# focuser-1_6.net
KiCad netlist of a schematic drawn in EAGLE
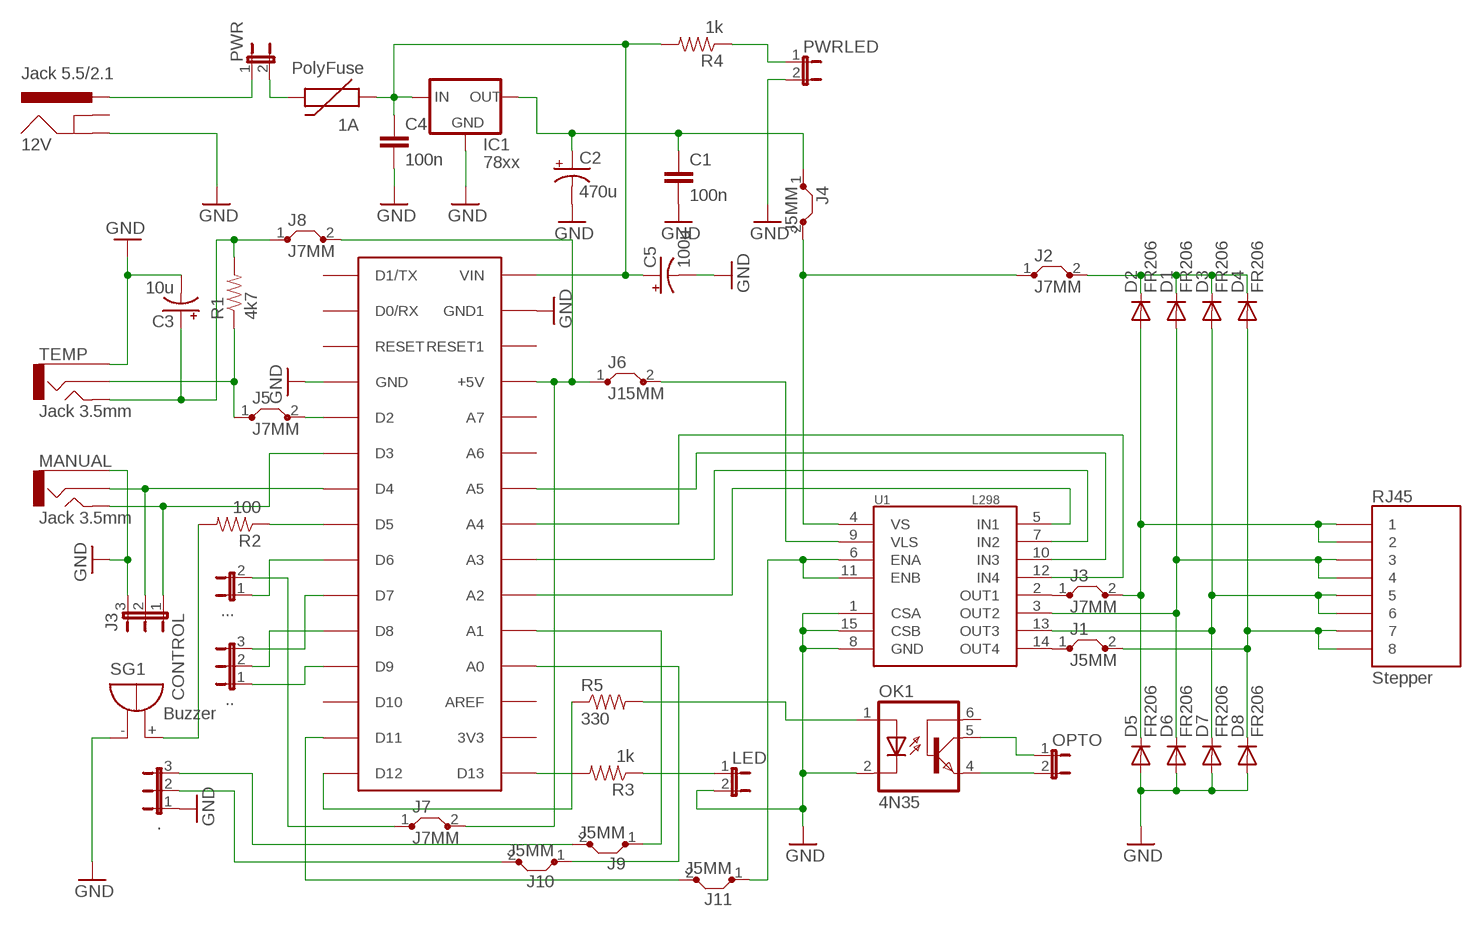
[diagram p0: schematic, sheet 1]

(export (version "E")
  (design (tool "Eeschema 10.0.6"))
  (components
    (comp (ref ".")
      (value "JUMPER-3PTH")
      (footprint "eagle-import:1X03")
      (libsource (lib "eagle-import") (part "JUMPER-3PTH"))
    )
    (comp (ref "..")
      (value "JUMPER-3PTH")
      (footprint "eagle-import:1X03")
      (libsource (lib "eagle-import") (part "JUMPER-3PTH"))
    )
    (comp (ref "...")
      (value "JUMPER-2PTH")
      (footprint "eagle-import:1X02")
      (libsource (lib "eagle-import") (part "JUMPER-2PTH"))
    )
    (comp (ref "1A")
      (value "PolyFuse")
      (footprint "eagle-import:PTC")
      (libsource (lib "eagle-import") (part "PTCPTH"))
    )
    (comp (ref "12V")
      (value "Jack 5.5/2.1")
      (footprint "eagle-import:POWER_JACK_COMBO")
      (libsource (lib "eagle-import") (part "POWER_JACKCOMBO"))
    )
    (comp (ref "C1")
      (value "100n")
      (footprint "eagle-import:AXIAL-5MM")
      (libsource (lib "eagle-import") (part "CAP_"))
    )
    (comp (ref "C2")
      (value "470u")
      (footprint "eagle-import:CPOL-RADIAL-100UF-25V")
      (libsource (lib "eagle-import") (part "CAP_POLPTH1"))
    )
    (comp (ref "C3")
      (value "10u")
      (footprint "eagle-import:CPOL-RADIAL-100UF-25V")
      (libsource (lib "eagle-import") (part "CAP_POLPTH1"))
    )
    (comp (ref "C4")
      (value "100n")
      (footprint "eagle-import:AXIAL-5MM")
      (libsource (lib "eagle-import") (part "CAP_"))
    )
    (comp (ref "C5")
      (value "100u")
      (footprint "eagle-import:CPOL-RADIAL-100UF-25V")
      (libsource (lib "eagle-import") (part "CAP_POLPTH1"))
    )
    (comp (ref "CONTROL")
      (value "J3")
      (footprint "eagle-import:1X03")
      (libsource (lib "eagle-import") (part "JUMPER-3PTH"))
    )
    (comp (ref "D1")
      (value "FR206")
      (footprint "eagle-import:DIODE-1N4001")
      (libsource (lib "eagle-import") (part "DIODEPTH"))
    )
    (comp (ref "D2")
      (value "FR206")
      (footprint "eagle-import:DIODE-1N4001")
      (libsource (lib "eagle-import") (part "DIODEPTH"))
    )
    (comp (ref "D3")
      (value "FR206")
      (footprint "eagle-import:DIODE-1N4001")
      (libsource (lib "eagle-import") (part "DIODEPTH"))
    )
    (comp (ref "D4")
      (value "FR206")
      (footprint "eagle-import:DIODE-1N4001")
      (libsource (lib "eagle-import") (part "DIODEPTH"))
    )
    (comp (ref "D5")
      (value "FR206")
      (footprint "eagle-import:DIODE-1N4001")
      (libsource (lib "eagle-import") (part "DIODEPTH"))
    )
    (comp (ref "D6")
      (value "FR206")
      (footprint "eagle-import:DIODE-1N4001")
      (libsource (lib "eagle-import") (part "DIODEPTH"))
    )
    (comp (ref "D7")
      (value "FR206")
      (footprint "eagle-import:DIODE-1N4001")
      (libsource (lib "eagle-import") (part "DIODEPTH"))
    )
    (comp (ref "D8")
      (value "FR206")
      (footprint "eagle-import:DIODE-1N4001")
      (libsource (lib "eagle-import") (part "DIODEPTH"))
    )
    (comp (ref "IC1")
      (value "78xx")
      (footprint "eagle-import:TO220-IGO")
      (libsource (lib "eagle-import") (part "V_REG_78XXSINK"))
    )
    (comp (ref "J1")
      (value "J5MM")
      (footprint "eagle-import:05")
      (libsource (lib "eagle-import") (part "J5MM"))
    )
    (comp (ref "J2")
      (value "J7MM")
      (footprint "eagle-import:07")
      (libsource (lib "eagle-import") (part "J7MM"))
    )
    (comp (ref "J3")
      (value "J7MM")
      (footprint "eagle-import:07")
      (libsource (lib "eagle-import") (part "J7MM"))
    )
    (comp (ref "J4")
      (value "J5MM")
      (footprint "eagle-import:05")
      (libsource (lib "eagle-import") (part "J5MM"))
    )
    (comp (ref "J5")
      (value "J7MM")
      (footprint "eagle-import:07")
      (libsource (lib "eagle-import") (part "J7MM"))
    )
    (comp (ref "J6")
      (value "J15MM")
      (footprint "eagle-import:15")
      (libsource (lib "eagle-import") (part "J15MM"))
    )
    (comp (ref "J7")
      (value "J7MM")
      (footprint "eagle-import:07")
      (libsource (lib "eagle-import") (part "J7MM"))
    )
    (comp (ref "J8")
      (value "J7MM")
      (footprint "eagle-import:07")
      (libsource (lib "eagle-import") (part "J7MM"))
    )
    (comp (ref "J9")
      (value "J5MM")
      (footprint "eagle-import:05")
      (libsource (lib "eagle-import") (part "J5MM"))
    )
    (comp (ref "J10")
      (value "J5MM")
      (footprint "eagle-import:05")
      (libsource (lib "eagle-import") (part "J5MM"))
    )
    (comp (ref "J11")
      (value "J5MM")
      (footprint "eagle-import:05")
      (libsource (lib "eagle-import") (part "J5MM"))
    )
    (comp (ref "LED")
      (value "JUMPER-2PTH")
      (footprint "eagle-import:1X02")
      (libsource (lib "eagle-import") (part "JUMPER-2PTH"))
    )
    (comp (ref "MANUAL")
      (value "Jack 3.5mm")
      (footprint "eagle-import:AUDIO-JACK")
      (libsource (lib "eagle-import") (part "AUDIO-JACKPTH"))
    )
    (comp (ref "OK1")
      (value "4N35")
      (footprint "eagle-import:DIL06")
      (fields (field (name "MF") "FAIRCHILD SEMICONDUCTOR"))
      (libsource (lib "eagle-import") (part "4N35"))
    )
    (comp (ref "OPTO")
      (value "JUMPER-2PTH")
      (footprint "eagle-import:1X02")
      (libsource (lib "eagle-import") (part "JUMPER-2PTH"))
    )
    (comp (ref "PWR")
      (value "JUMPER-2PTH")
      (footprint "eagle-import:1X02")
      (libsource (lib "eagle-import") (part "JUMPER-2PTH"))
    )
    (comp (ref "PWRLED")
      (value "JUMPER-2PTH")
      (footprint "eagle-import:1X02")
      (libsource (lib "eagle-import") (part "JUMPER-2PTH"))
    )
    (comp (ref "R1")
      (value "4k7")
      (footprint "eagle-import:AXIAL-0.3")
      (libsource (lib "eagle-import") (part "RESISTORPTH1"))
    )
    (comp (ref "R2")
      (value "100")
      (footprint "eagle-import:AXIAL-0.3")
      (libsource (lib "eagle-import") (part "RESISTORPTH1"))
    )
    (comp (ref "R3")
      (value "1k")
      (footprint "eagle-import:AXIAL-0.3")
      (libsource (lib "eagle-import") (part "RESISTORPTH1"))
    )
    (comp (ref "R4")
      (value "1k")
      (footprint "eagle-import:AXIAL-0.3")
      (libsource (lib "eagle-import") (part "RESISTORPTH1"))
    )
    (comp (ref "R5")
      (value "330")
      (footprint "eagle-import:AXIAL-0.3")
      (libsource (lib "eagle-import") (part "RESISTORPTH1"))
    )
    (comp (ref "RJ45")
      (value "Stepper")
      (footprint "eagle-import:RJ45-8")
      (libsource (lib "eagle-import") (part "RJ45-8PTH"))
    )
    (comp (ref "SG1")
      (value "Buzzer")
      (footprint "eagle-import:F_QMBIII")
      (libsource (lib "eagle-import") (part "F/QMBIII"))
    )
    (comp (ref "TEMP")
      (value "Jack 3.5mm")
      (footprint "eagle-import:AUDIO-JACK")
      (libsource (lib "eagle-import") (part "AUDIO-JACKPTH"))
    )
    (comp (ref "U$1")
      (value "ARDUINONANO")
      (footprint "eagle-import:PDIP-32")
      (libsource (lib "eagle-import") (part "ARDUINONANO"))
    )
    (comp (ref "U1")
      (value "L298")
      (footprint "eagle-import:MULTIWATT15")
      (libsource (lib "eagle-import") (part "L298"))
    )
  )
  (nets
    (net (code "1") (name "GND") (class "Default")
      (node (ref ".") (pin "1") (pinfunction "1_1") (pintype "passive"))
      (node (ref "12V") (pin "GND@1") (pinfunction "GND_GND@1") (pintype "bidirectional"))
      (node (ref "C1") (pin "P$2") (pinfunction "2_P$2") (pintype "passive"))
      (node (ref "C2") (pin "2") (pinfunction "-_2") (pintype "passive"))
      (node (ref "C3") (pin "2") (pinfunction "-_2") (pintype "passive"))
      (node (ref "C4") (pin "P$2") (pinfunction "2_P$2") (pintype "passive"))
      (node (ref "C5") (pin "2") (pinfunction "-_2") (pintype "passive"))
      (node (ref "CONTROL") (pin "3") (pinfunction "3_3") (pintype "passive"))
      (node (ref "D5") (pin "A") (pinfunction "A_A") (pintype "passive"))
      (node (ref "D6") (pin "A") (pinfunction "A_A") (pintype "passive"))
      (node (ref "D7") (pin "A") (pinfunction "A_A") (pintype "passive"))
      (node (ref "D8") (pin "A") (pinfunction "A_A") (pintype "passive"))
      (node (ref "IC1") (pin "GND") (pinfunction "GND_GND") (pintype "input"))
      (node (ref "LED") (pin "2") (pinfunction "2_2") (pintype "passive"))
      (node (ref "MANUAL") (pin "1") (pinfunction "1_1") (pintype "bidirectional"))
      (node (ref "OK1") (pin "2") (pinfunction "C_2") (pintype "passive"))
      (node (ref "PWRLED") (pin "2") (pinfunction "2_2") (pintype "passive"))
      (node (ref "SG1") (pin "-") (pinfunction "+_-") (pintype "passive"))
      (node (ref "TEMP") (pin "1") (pinfunction "1_1") (pintype "bidirectional"))
      (node (ref "U$1") (pin "GND") (pinfunction "GND_GND") (pintype "bidirectional"))
      (node (ref "U$1") (pin "GND1") (pinfunction "GND1_GND1") (pintype "bidirectional"))
      (node (ref "U1") (pin "1") (pinfunction "CSA_1") (pintype "bidirectional"))
      (node (ref "U1") (pin "15") (pinfunction "CSB_15") (pintype "bidirectional"))
      (node (ref "U1") (pin "8") (pinfunction "GND_8") (pintype "bidirectional"))
    )
    (net (code "2") (name "Net-(.-Pad2)") (class "Default")
      (node (ref ".") (pin "2") (pinfunction "2_2") (pintype "passive"))
      (node (ref "J10") (pin "2") (pinfunction "2_2") (pintype "passive"))
    )
    (net (code "3") (name "Net-(.-Pad3)") (class "Default")
      (node (ref ".") (pin "3") (pinfunction "3_3") (pintype "passive"))
      (node (ref "J9") (pin "2") (pinfunction "2_2") (pintype "passive"))
    )
    (net (code "4") (name "Net-(..-Pad1)") (class "Default")
      (node (ref "..") (pin "1") (pinfunction "1_1") (pintype "passive"))
      (node (ref "U$1") (pin "D9") (pinfunction "D9_D9") (pintype "bidirectional"))
    )
    (net (code "5") (name "Net-(..-Pad2)") (class "Default")
      (node (ref "..") (pin "2") (pinfunction "2_2") (pintype "passive"))
      (node (ref "U$1") (pin "D8") (pinfunction "D8_D8") (pintype "bidirectional"))
    )
    (net (code "6") (name "Net-(..-Pad3)") (class "Default")
      (node (ref "..") (pin "3") (pinfunction "3_3") (pintype "passive"))
      (node (ref "U$1") (pin "D7") (pinfunction "D7_D7") (pintype "bidirectional"))
    )
    (net (code "7") (name "Net-(...-Pad1)") (class "Default")
      (node (ref "...") (pin "1") (pinfunction "1_1") (pintype "passive"))
      (node (ref "U$1") (pin "D6") (pinfunction "D6_D6") (pintype "bidirectional"))
    )
    (net (code "8") (name "Net-(...-Pad2)") (class "Default")
      (node (ref "...") (pin "2") (pinfunction "2_2") (pintype "passive"))
      (node (ref "J7") (pin "1") (pinfunction "1_1") (pintype "passive"))
    )
    (net (code "9") (name "Net-(1A-1)") (class "Default")
      (node (ref "1A") (pin "P$1") (pinfunction "1_P$1") (pintype "bidirectional"))
      (node (ref "C4") (pin "P$1") (pinfunction "1_P$1") (pintype "passive"))
      (node (ref "C5") (pin "1") (pinfunction "+_1") (pintype "passive"))
      (node (ref "IC1") (pin "IN") (pinfunction "IN_IN") (pintype "input"))
      (node (ref "R4") (pin "P$2") (pinfunction "2_P$2") (pintype "passive"))
      (node (ref "U$1") (pin "VIN") (pinfunction "VIN_VIN") (pintype "bidirectional"))
    )
    (net (code "10") (name "Net-(1A-2)") (class "Default")
      (node (ref "1A") (pin "P$2") (pinfunction "2_P$2") (pintype "bidirectional"))
      (node (ref "PWR") (pin "2") (pinfunction "2_2") (pintype "passive"))
    )
    (net (code "11") (name "Net-(12V-PWR)") (class "Default")
      (node (ref "12V") (pin "POWER") (pinfunction "PWR_POWER") (pintype "bidirectional"))
      (node (ref "PWR") (pin "1") (pinfunction "1_1") (pintype "passive"))
    )
    (net (code "12") (name "Net-(C1-1)") (class "Default")
      (node (ref "C1") (pin "P$1") (pinfunction "1_P$1") (pintype "passive"))
      (node (ref "C2") (pin "1") (pinfunction "+_1") (pintype "passive"))
      (node (ref "IC1") (pin "OUT") (pinfunction "OUT_OUT") (pintype "output"))
      (node (ref "J4") (pin "1") (pinfunction "1_1") (pintype "passive"))
    )
    (net (code "13") (name "Net-(C3-+)") (class "Default")
      (node (ref "C3") (pin "1") (pinfunction "+_1") (pintype "passive"))
      (node (ref "J8") (pin "1") (pinfunction "1_1") (pintype "passive"))
      (node (ref "R1") (pin "P$2") (pinfunction "2_P$2") (pintype "passive"))
      (node (ref "TEMP") (pin "5") (pinfunction "5_5") (pintype "bidirectional"))
    )
    (net (code "14") (name "Net-(CONTROL-Pad1)") (class "Default")
      (node (ref "CONTROL") (pin "1") (pinfunction "1_1") (pintype "passive"))
      (node (ref "MANUAL") (pin "5") (pinfunction "5_5") (pintype "bidirectional"))
      (node (ref "U$1") (pin "D3") (pinfunction "D3_D3") (pintype "bidirectional"))
    )
    (net (code "15") (name "Net-(CONTROL-Pad2)") (class "Default")
      (node (ref "CONTROL") (pin "2") (pinfunction "2_2") (pintype "passive"))
      (node (ref "MANUAL") (pin "2") (pinfunction "2_2") (pintype "bidirectional"))
      (node (ref "U$1") (pin "D4") (pinfunction "D4_D4") (pintype "bidirectional"))
    )
    (net (code "16") (name "Net-(D1-PadC)") (class "Default")
      (node (ref "D1") (pin "C") (pinfunction "C_C") (pintype "passive"))
      (node (ref "D2") (pin "C") (pinfunction "C_C") (pintype "passive"))
      (node (ref "D3") (pin "C") (pinfunction "C_C") (pintype "passive"))
      (node (ref "D4") (pin "C") (pinfunction "C_C") (pintype "passive"))
      (node (ref "J2") (pin "2") (pinfunction "2_2") (pintype "passive"))
    )
    (net (code "17") (name "Net-(D2-PadA)") (class "Default")
      (node (ref "D2") (pin "A") (pinfunction "A_A") (pintype "passive"))
      (node (ref "D5") (pin "C") (pinfunction "C_C") (pintype "passive"))
      (node (ref "J3") (pin "2") (pinfunction "2_2") (pintype "passive"))
      (node (ref "RJ45") (pin "1") (pinfunction "1_1") (pintype "bidirectional"))
      (node (ref "RJ45") (pin "2") (pinfunction "2_2") (pintype "bidirectional"))
    )
    (net (code "18") (name "Net-(D4-PadA)") (class "Default")
      (node (ref "D4") (pin "A") (pinfunction "A_A") (pintype "passive"))
      (node (ref "D8") (pin "C") (pinfunction "C_C") (pintype "passive"))
      (node (ref "J1") (pin "2") (pinfunction "2_2") (pintype "passive"))
      (node (ref "RJ45") (pin "7") (pinfunction "7_7") (pintype "bidirectional"))
      (node (ref "RJ45") (pin "8") (pinfunction "8_8") (pintype "bidirectional"))
    )
    (net (code "19") (name "Net-(J5-Pad2)") (class "Default")
      (node (ref "J5") (pin "2") (pinfunction "2_2") (pintype "passive"))
      (node (ref "U$1") (pin "D2") (pinfunction "D2_D2") (pintype "bidirectional"))
    )
    (net (code "20") (name "Net-(J6-Pad1)") (class "Default")
      (node (ref "J6") (pin "1") (pinfunction "1_1") (pintype "passive"))
      (node (ref "J7") (pin "2") (pinfunction "2_2") (pintype "passive"))
      (node (ref "J8") (pin "2") (pinfunction "2_2") (pintype "passive"))
      (node (ref "U$1") (pin "+5V") (pinfunction "+5V_+5V") (pintype "bidirectional"))
    )
    (net (code "21") (name "Net-(J11-Pad2)") (class "Default")
      (node (ref "J11") (pin "2") (pinfunction "2_2") (pintype "passive"))
      (node (ref "U$1") (pin "D11") (pinfunction "D11_D11") (pintype "bidirectional"))
    )
    (net (code "22") (name "Net-(OK1-A)") (class "Default")
      (node (ref "OK1") (pin "1") (pinfunction "A_1") (pintype "passive"))
      (node (ref "R5") (pin "P$2") (pinfunction "2_P$2") (pintype "passive"))
    )
    (net (code "23") (name "Net-(OK1-COL)") (class "Default")
      (node (ref "OK1") (pin "5") (pinfunction "COL_5") (pintype "passive"))
      (node (ref "OPTO") (pin "1") (pinfunction "1_1") (pintype "passive"))
    )
    (net (code "24") (name "Net-(OK1-EMI)") (class "Default")
      (node (ref "OK1") (pin "4") (pinfunction "EMI_4") (pintype "passive"))
      (node (ref "OPTO") (pin "2") (pinfunction "2_2") (pintype "passive"))
    )
    (net (code "25") (name "Net-(R1-1)") (class "Default")
      (node (ref "J5") (pin "1") (pinfunction "1_1") (pintype "passive"))
      (node (ref "R1") (pin "P$1") (pinfunction "1_P$1") (pintype "passive"))
      (node (ref "TEMP") (pin "2") (pinfunction "2_2") (pintype "bidirectional"))
    )
    (net (code "26") (name "Net-(R2-1)") (class "Default")
      (node (ref "R2") (pin "P$1") (pinfunction "1_P$1") (pintype "passive"))
      (node (ref "U$1") (pin "D5") (pinfunction "D5_D5") (pintype "bidirectional"))
    )
    (net (code "27") (name "Net-(R2-2)") (class "Default")
      (node (ref "R2") (pin "P$2") (pinfunction "2_P$2") (pintype "passive"))
      (node (ref "SG1") (pin "+") (pinfunction "-_+") (pintype "passive"))
    )
    (net (code "28") (name "Net-(R3-1)") (class "Default")
      (node (ref "LED") (pin "1") (pinfunction "1_1") (pintype "passive"))
      (node (ref "R3") (pin "P$1") (pinfunction "1_P$1") (pintype "passive"))
    )
    (net (code "29") (name "Net-(R3-2)") (class "Default")
      (node (ref "R3") (pin "P$2") (pinfunction "2_P$2") (pintype "passive"))
      (node (ref "U$1") (pin "D13") (pinfunction "D13_D13") (pintype "bidirectional"))
    )
    (net (code "30") (name "Net-(R4-1)") (class "Default")
      (node (ref "PWRLED") (pin "1") (pinfunction "1_1") (pintype "passive"))
      (node (ref "R4") (pin "P$1") (pinfunction "1_P$1") (pintype "passive"))
    )
    (net (code "31") (name "Net-(R5-1)") (class "Default")
      (node (ref "R5") (pin "P$1") (pinfunction "1_P$1") (pintype "passive"))
      (node (ref "U$1") (pin "D12") (pinfunction "D12_D12") (pintype "bidirectional"))
    )
    (net (code "32") (name "Net-(U$1-A0)") (class "Default")
      (node (ref "J10") (pin "1") (pinfunction "1_1") (pintype "passive"))
      (node (ref "U$1") (pin "A7") (pinfunction "A0_A7") (pintype "bidirectional"))
    )
    (net (code "33") (name "Net-(U$1-A1)") (class "Default")
      (node (ref "J9") (pin "1") (pinfunction "1_1") (pintype "passive"))
      (node (ref "U$1") (pin "A6") (pinfunction "A1_A6") (pintype "bidirectional"))
    )
    (net (code "34") (name "Net-(U$1-A2)") (class "Default")
      (node (ref "U$1") (pin "A5") (pinfunction "A2_A5") (pintype "bidirectional"))
      (node (ref "U1") (pin "5") (pinfunction "IN1_5") (pintype "bidirectional"))
    )
    (net (code "35") (name "Net-(U$1-A3)") (class "Default")
      (node (ref "U$1") (pin "A4") (pinfunction "A3_A4") (pintype "bidirectional"))
      (node (ref "U1") (pin "7") (pinfunction "IN2_7") (pintype "bidirectional"))
    )
    (net (code "36") (name "Net-(U$1-A4)") (class "Default")
      (node (ref "U$1") (pin "A3") (pinfunction "A4_A3") (pintype "bidirectional"))
      (node (ref "U1") (pin "12") (pinfunction "IN4_12") (pintype "bidirectional"))
    )
    (net (code "37") (name "Net-(U$1-A5)") (class "Default")
      (node (ref "U$1") (pin "A2") (pinfunction "A5_A2") (pintype "bidirectional"))
      (node (ref "U1") (pin "10") (pinfunction "IN3_10") (pintype "bidirectional"))
    )
    (net (code "38") (name "Net-(U1-ENA)") (class "Default")
      (node (ref "J11") (pin "1") (pinfunction "1_1") (pintype "passive"))
      (node (ref "U1") (pin "11") (pinfunction "ENB_11") (pintype "bidirectional"))
      (node (ref "U1") (pin "6") (pinfunction "ENA_6") (pintype "bidirectional"))
    )
    (net (code "39") (name "Net-(U1-OUT1)") (class "Default")
      (node (ref "J3") (pin "1") (pinfunction "1_1") (pintype "passive"))
      (node (ref "U1") (pin "2") (pinfunction "OUT1_2") (pintype "bidirectional"))
    )
    (net (code "40") (name "Net-(U1-OUT2)") (class "Default")
      (node (ref "D1") (pin "A") (pinfunction "A_A") (pintype "passive"))
      (node (ref "D6") (pin "C") (pinfunction "C_C") (pintype "passive"))
      (node (ref "RJ45") (pin "3") (pinfunction "3_3") (pintype "bidirectional"))
      (node (ref "RJ45") (pin "4") (pinfunction "4_4") (pintype "bidirectional"))
      (node (ref "U1") (pin "3") (pinfunction "OUT2_3") (pintype "bidirectional"))
    )
    (net (code "41") (name "Net-(U1-OUT3)") (class "Default")
      (node (ref "D3") (pin "A") (pinfunction "A_A") (pintype "passive"))
      (node (ref "D7") (pin "C") (pinfunction "C_C") (pintype "passive"))
      (node (ref "RJ45") (pin "5") (pinfunction "5_5") (pintype "bidirectional"))
      (node (ref "RJ45") (pin "6") (pinfunction "6_6") (pintype "bidirectional"))
      (node (ref "U1") (pin "13") (pinfunction "OUT3_13") (pintype "bidirectional"))
    )
    (net (code "42") (name "Net-(U1-OUT4)") (class "Default")
      (node (ref "J1") (pin "1") (pinfunction "1_1") (pintype "passive"))
      (node (ref "U1") (pin "14") (pinfunction "OUT4_14") (pintype "bidirectional"))
    )
    (net (code "43") (name "Net-(U1-VLS)") (class "Default")
      (node (ref "J6") (pin "2") (pinfunction "2_2") (pintype "passive"))
      (node (ref "U1") (pin "9") (pinfunction "VLS_9") (pintype "bidirectional"))
    )
    (net (code "44") (name "Net-(U1-VS)") (class "Default")
      (node (ref "J2") (pin "1") (pinfunction "1_1") (pintype "passive"))
      (node (ref "J4") (pin "2") (pinfunction "2_2") (pintype "passive"))
      (node (ref "U1") (pin "4") (pinfunction "VS_4") (pintype "bidirectional"))
    )
    (net (code "45") (name "unconnected-(12V-GNDBREAK-PadGND)") (class "Default")
      (node (ref "12V") (pin "GND") (pinfunction "GNDBREAK_GND") (pintype "bidirectional"))
    )
    (net (code "46") (name "unconnected-(OK1-BAS-Pad6)") (class "Default")
      (node (ref "OK1") (pin "6") (pinfunction "BAS_6") (pintype "passive"))
    )
    (net (code "47") (name "unconnected-(U$1-A6-PadA1)") (class "Default")
      (node (ref "U$1") (pin "A1") (pinfunction "A6_A1") (pintype "bidirectional"))
    )
    (net (code "48") (name "unconnected-(U$1-A7-PadA0)") (class "Default")
      (node (ref "U$1") (pin "A0") (pinfunction "A7_A0") (pintype "bidirectional"))
    )
    (net (code "49") (name "unconnected-(U$1-Pad3V3)") (class "Default")
      (node (ref "U$1") (pin "3V3") (pinfunction "3V3_3V3") (pintype "bidirectional"))
    )
    (net (code "50") (name "unconnected-(U$1-PadAREF)") (class "Default")
      (node (ref "U$1") (pin "AREF") (pinfunction "AREF_AREF") (pintype "bidirectional"))
    )
    (net (code "51") (name "unconnected-(U$1-PadD0{slash}RX)") (class "Default")
      (node (ref "U$1") (pin "D0/RX") (pinfunction "D0/RX_D0/RX") (pintype "bidirectional"))
    )
    (net (code "52") (name "unconnected-(U$1-PadD1{slash}TX)") (class "Default")
      (node (ref "U$1") (pin "D1/TX") (pinfunction "D1/TX_D1/TX") (pintype "bidirectional"))
    )
    (net (code "53") (name "unconnected-(U$1-PadD10)") (class "Default")
      (node (ref "U$1") (pin "D10") (pinfunction "D10_D10") (pintype "bidirectional"))
    )
    (net (code "54") (name "unconnected-(U$1-PadRESET)") (class "Default")
      (node (ref "U$1") (pin "RESET") (pinfunction "RESET_RESET") (pintype "bidirectional"))
    )
    (net (code "55") (name "unconnected-(U$1-PadRESET1)") (class "Default")
      (node (ref "U$1") (pin "RESET1") (pinfunction "RESET1_RESET1") (pintype "bidirectional"))
    )
  )
)
